# ESPMINERS.net
KiCad netlist of a schematic drawn in EasyEDA
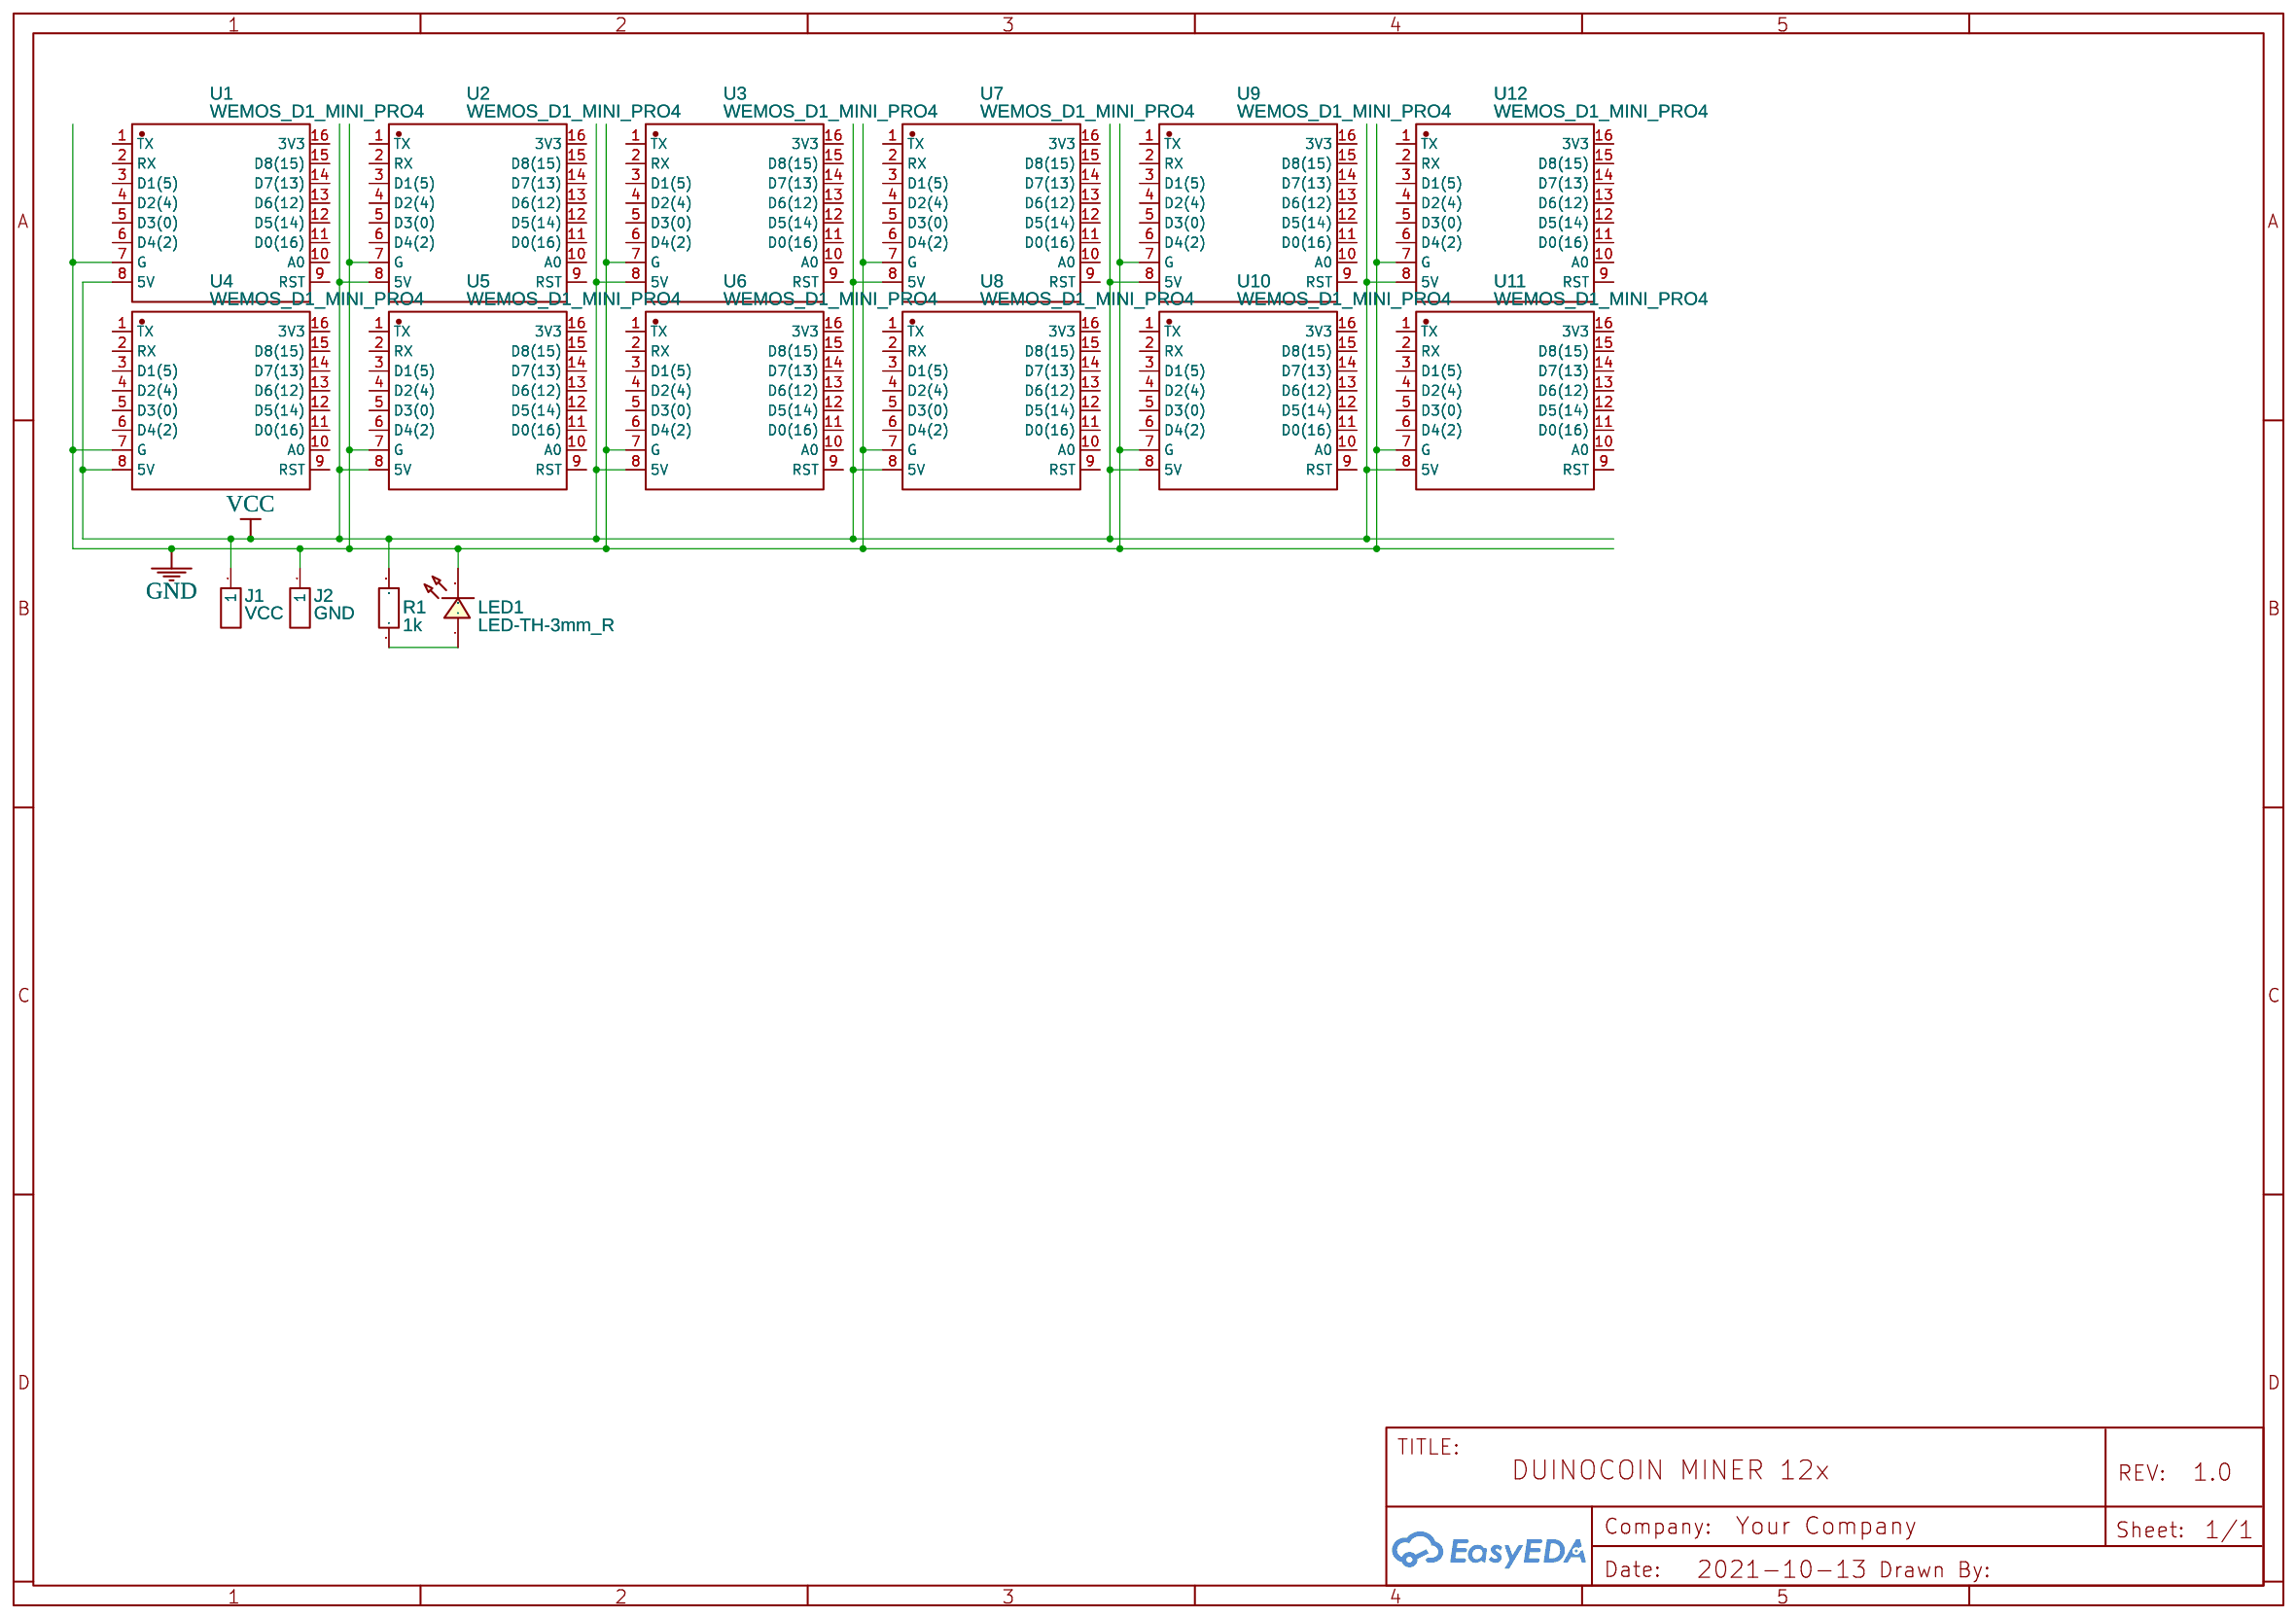
[diagram p0: schematic sheet]

(export (version "E")
  (design (tool "Eeschema 10.0.6"))
  (components
    (comp (ref "J1")
      (value "VCC")
      (fields (field (name "BOM_Supplier Part") "C81276"))
      (libsource (lib "") (part "HDR-M-2.54_1x1"))
    )
    (comp (ref "J2")
      (value "GND")
      (fields (field (name "BOM_Supplier Part") "C81276"))
      (libsource (lib "") (part "HDR-M-2.54_1x1"))
    )
    (comp (ref "LED1")
      (value "LED-TH-3mm_R")
      (fields
        (field (name "BOM_Manufacturer Part") "204-10SDRD/S530-A3-L")
        (field (name "BOM_Supplier Part") "C84774")
      )
      (libsource (lib "") (part "LED-TH-3mm_R"))
    )
    (comp (ref "R1") (value "1k") (libsource (lib "") (part "R_AXIAL-0.3_EU")))
    (comp (ref "U1")
      (value "WEMOS_D1_MINI_PRO4")
      (fields
        (field (name "BOM_Manufacturer Part") "Wemos_D1_mini_Pro4")
        (field (name "BOM_Supplier Part") "C2837266")
      )
      (libsource (lib "") (part "WEMOS_D1_MINI_PRO4"))
    )
    (comp (ref "U2")
      (value "WEMOS_D1_MINI_PRO4")
      (fields
        (field (name "BOM_Manufacturer Part") "Wemos_D1_mini_Pro4")
        (field (name "BOM_Supplier Part") "C2837266")
      )
      (libsource (lib "") (part "WEMOS_D1_MINI_PRO4"))
    )
    (comp (ref "U3")
      (value "WEMOS_D1_MINI_PRO4")
      (fields
        (field (name "BOM_Manufacturer Part") "Wemos_D1_mini_Pro4")
        (field (name "BOM_Supplier Part") "C2837266")
      )
      (libsource (lib "") (part "WEMOS_D1_MINI_PRO4"))
    )
    (comp (ref "U4")
      (value "WEMOS_D1_MINI_PRO4")
      (fields
        (field (name "BOM_Manufacturer Part") "Wemos_D1_mini_Pro4")
        (field (name "BOM_Supplier Part") "C2837266")
      )
      (libsource (lib "") (part "WEMOS_D1_MINI_PRO4"))
    )
    (comp (ref "U5")
      (value "WEMOS_D1_MINI_PRO4")
      (fields
        (field (name "BOM_Manufacturer Part") "Wemos_D1_mini_Pro4")
        (field (name "BOM_Supplier Part") "C2837266")
      )
      (libsource (lib "") (part "WEMOS_D1_MINI_PRO4"))
    )
    (comp (ref "U6")
      (value "WEMOS_D1_MINI_PRO4")
      (fields
        (field (name "BOM_Manufacturer Part") "Wemos_D1_mini_Pro4")
        (field (name "BOM_Supplier Part") "C2837266")
      )
      (libsource (lib "") (part "WEMOS_D1_MINI_PRO4"))
    )
    (comp (ref "U7")
      (value "WEMOS_D1_MINI_PRO4")
      (fields
        (field (name "BOM_Manufacturer Part") "Wemos_D1_mini_Pro4")
        (field (name "BOM_Supplier Part") "C2837266")
      )
      (libsource (lib "") (part "WEMOS_D1_MINI_PRO4"))
    )
    (comp (ref "U8")
      (value "WEMOS_D1_MINI_PRO4")
      (fields
        (field (name "BOM_Manufacturer Part") "Wemos_D1_mini_Pro4")
        (field (name "BOM_Supplier Part") "C2837266")
      )
      (libsource (lib "") (part "WEMOS_D1_MINI_PRO4"))
    )
    (comp (ref "U9")
      (value "WEMOS_D1_MINI_PRO4")
      (fields
        (field (name "BOM_Manufacturer Part") "Wemos_D1_mini_Pro4")
        (field (name "BOM_Supplier Part") "C2837266")
      )
      (libsource (lib "") (part "WEMOS_D1_MINI_PRO4"))
    )
    (comp (ref "U10")
      (value "WEMOS_D1_MINI_PRO4")
      (fields
        (field (name "BOM_Manufacturer Part") "Wemos_D1_mini_Pro4")
        (field (name "BOM_Supplier Part") "C2837266")
      )
      (libsource (lib "") (part "WEMOS_D1_MINI_PRO4"))
    )
    (comp (ref "U11")
      (value "WEMOS_D1_MINI_PRO4")
      (fields
        (field (name "BOM_Manufacturer Part") "Wemos_D1_mini_Pro4")
        (field (name "BOM_Supplier Part") "C2837266")
      )
      (libsource (lib "") (part "WEMOS_D1_MINI_PRO4"))
    )
    (comp (ref "U12")
      (value "WEMOS_D1_MINI_PRO4")
      (fields
        (field (name "BOM_Manufacturer Part") "Wemos_D1_mini_Pro4")
        (field (name "BOM_Supplier Part") "C2837266")
      )
      (libsource (lib "") (part "WEMOS_D1_MINI_PRO4"))
    )
  )
  (nets
    (net (code "1") (name "GND") (class "Default")
      (node (ref "J2") (pin "1") (pinfunction "1_1") (pintype "input"))
      (node (ref "LED1") (pin "2") (pinfunction "2_2") (pintype "unspecified"))
      (node (ref "U1") (pin "7") (pinfunction "G_7") (pintype "unspecified"))
      (node (ref "U10") (pin "7") (pinfunction "G_7") (pintype "unspecified"))
      (node (ref "U11") (pin "7") (pinfunction "G_7") (pintype "unspecified"))
      (node (ref "U12") (pin "7") (pinfunction "G_7") (pintype "unspecified"))
      (node (ref "U2") (pin "7") (pinfunction "G_7") (pintype "unspecified"))
      (node (ref "U3") (pin "7") (pinfunction "G_7") (pintype "unspecified"))
      (node (ref "U4") (pin "7") (pinfunction "G_7") (pintype "unspecified"))
      (node (ref "U5") (pin "7") (pinfunction "G_7") (pintype "unspecified"))
      (node (ref "U6") (pin "7") (pinfunction "G_7") (pintype "unspecified"))
      (node (ref "U7") (pin "7") (pinfunction "G_7") (pintype "unspecified"))
      (node (ref "U8") (pin "7") (pinfunction "G_7") (pintype "unspecified"))
      (node (ref "U9") (pin "7") (pinfunction "G_7") (pintype "unspecified"))
    )
    (net (code "2") (name "Net-(LED1-Pad1)") (class "Default")
      (node (ref "LED1") (pin "1") (pinfunction "1_1") (pintype "unspecified"))
      (node (ref "R1") (pin "1") (pinfunction "1_1") (pintype "unspecified"))
    )
    (net (code "3") (name "VCC") (class "Default")
      (node (ref "J1") (pin "1") (pinfunction "1_1") (pintype "input"))
      (node (ref "R1") (pin "2") (pinfunction "2_2") (pintype "unspecified"))
      (node (ref "U1") (pin "8") (pinfunction "5V_8") (pintype "unspecified"))
      (node (ref "U10") (pin "8") (pinfunction "5V_8") (pintype "unspecified"))
      (node (ref "U11") (pin "8") (pinfunction "5V_8") (pintype "unspecified"))
      (node (ref "U12") (pin "8") (pinfunction "5V_8") (pintype "unspecified"))
      (node (ref "U2") (pin "8") (pinfunction "5V_8") (pintype "unspecified"))
      (node (ref "U3") (pin "8") (pinfunction "5V_8") (pintype "unspecified"))
      (node (ref "U4") (pin "8") (pinfunction "5V_8") (pintype "unspecified"))
      (node (ref "U5") (pin "8") (pinfunction "5V_8") (pintype "unspecified"))
      (node (ref "U6") (pin "8") (pinfunction "5V_8") (pintype "unspecified"))
      (node (ref "U7") (pin "8") (pinfunction "5V_8") (pintype "unspecified"))
      (node (ref "U8") (pin "8") (pinfunction "5V_8") (pintype "unspecified"))
      (node (ref "U9") (pin "8") (pinfunction "5V_8") (pintype "unspecified"))
    )
    (net (code "4") (name "unconnected-(U1-3V3-Pad16)") (class "Default")
      (node (ref "U1") (pin "16") (pinfunction "3V3_16") (pintype "unspecified"))
    )
    (net (code "5") (name "unconnected-(U1-A0-Pad10)") (class "Default")
      (node (ref "U1") (pin "10") (pinfunction "A0_10") (pintype "unspecified"))
    )
    (net (code "6") (name "unconnected-(U1-D0(16)-Pad11)") (class "Default")
      (node (ref "U1") (pin "11") (pinfunction "D0(16)_11") (pintype "unspecified"))
    )
    (net (code "7") (name "unconnected-(U1-D1(5)-Pad3)") (class "Default")
      (node (ref "U1") (pin "3") (pinfunction "D1(5)_3") (pintype "unspecified"))
    )
    (net (code "8") (name "unconnected-(U1-D2(4)-Pad4)") (class "Default")
      (node (ref "U1") (pin "4") (pinfunction "D2(4)_4") (pintype "unspecified"))
    )
    (net (code "9") (name "unconnected-(U1-D3(0)-Pad5)") (class "Default")
      (node (ref "U1") (pin "5") (pinfunction "D3(0)_5") (pintype "unspecified"))
    )
    (net (code "10") (name "unconnected-(U1-D4(2)-Pad6)") (class "Default")
      (node (ref "U1") (pin "6") (pinfunction "D4(2)_6") (pintype "unspecified"))
    )
    (net (code "11") (name "unconnected-(U1-D5(14)-Pad12)") (class "Default")
      (node (ref "U1") (pin "12") (pinfunction "D5(14)_12") (pintype "unspecified"))
    )
    (net (code "12") (name "unconnected-(U1-D6(12)-Pad13)") (class "Default")
      (node (ref "U1") (pin "13") (pinfunction "D6(12)_13") (pintype "unspecified"))
    )
    (net (code "13") (name "unconnected-(U1-D7(13)-Pad14)") (class "Default")
      (node (ref "U1") (pin "14") (pinfunction "D7(13)_14") (pintype "unspecified"))
    )
    (net (code "14") (name "unconnected-(U1-D8(15)-Pad15)") (class "Default")
      (node (ref "U1") (pin "15") (pinfunction "D8(15)_15") (pintype "unspecified"))
    )
    (net (code "15") (name "unconnected-(U1-RST-Pad9)") (class "Default")
      (node (ref "U1") (pin "9") (pinfunction "RST_9") (pintype "unspecified"))
    )
    (net (code "16") (name "unconnected-(U1-RX-Pad2)") (class "Default")
      (node (ref "U1") (pin "2") (pinfunction "RX_2") (pintype "unspecified"))
    )
    (net (code "17") (name "unconnected-(U1-TX-Pad1)") (class "Default")
      (node (ref "U1") (pin "1") (pinfunction "TX_1") (pintype "unspecified"))
    )
    (net (code "18") (name "unconnected-(U2-3V3-Pad16)") (class "Default")
      (node (ref "U2") (pin "16") (pinfunction "3V3_16") (pintype "unspecified"))
    )
    (net (code "19") (name "unconnected-(U2-A0-Pad10)") (class "Default")
      (node (ref "U2") (pin "10") (pinfunction "A0_10") (pintype "unspecified"))
    )
    (net (code "20") (name "unconnected-(U2-D0(16)-Pad11)") (class "Default")
      (node (ref "U2") (pin "11") (pinfunction "D0(16)_11") (pintype "unspecified"))
    )
    (net (code "21") (name "unconnected-(U2-D1(5)-Pad3)") (class "Default")
      (node (ref "U2") (pin "3") (pinfunction "D1(5)_3") (pintype "unspecified"))
    )
    (net (code "22") (name "unconnected-(U2-D2(4)-Pad4)") (class "Default")
      (node (ref "U2") (pin "4") (pinfunction "D2(4)_4") (pintype "unspecified"))
    )
    (net (code "23") (name "unconnected-(U2-D3(0)-Pad5)") (class "Default")
      (node (ref "U2") (pin "5") (pinfunction "D3(0)_5") (pintype "unspecified"))
    )
    (net (code "24") (name "unconnected-(U2-D4(2)-Pad6)") (class "Default")
      (node (ref "U2") (pin "6") (pinfunction "D4(2)_6") (pintype "unspecified"))
    )
    (net (code "25") (name "unconnected-(U2-D5(14)-Pad12)") (class "Default")
      (node (ref "U2") (pin "12") (pinfunction "D5(14)_12") (pintype "unspecified"))
    )
    (net (code "26") (name "unconnected-(U2-D6(12)-Pad13)") (class "Default")
      (node (ref "U2") (pin "13") (pinfunction "D6(12)_13") (pintype "unspecified"))
    )
    (net (code "27") (name "unconnected-(U2-D7(13)-Pad14)") (class "Default")
      (node (ref "U2") (pin "14") (pinfunction "D7(13)_14") (pintype "unspecified"))
    )
    (net (code "28") (name "unconnected-(U2-D8(15)-Pad15)") (class "Default")
      (node (ref "U2") (pin "15") (pinfunction "D8(15)_15") (pintype "unspecified"))
    )
    (net (code "29") (name "unconnected-(U2-RST-Pad9)") (class "Default")
      (node (ref "U2") (pin "9") (pinfunction "RST_9") (pintype "unspecified"))
    )
    (net (code "30") (name "unconnected-(U2-RX-Pad2)") (class "Default")
      (node (ref "U2") (pin "2") (pinfunction "RX_2") (pintype "unspecified"))
    )
    (net (code "31") (name "unconnected-(U2-TX-Pad1)") (class "Default")
      (node (ref "U2") (pin "1") (pinfunction "TX_1") (pintype "unspecified"))
    )
    (net (code "32") (name "unconnected-(U3-3V3-Pad16)") (class "Default")
      (node (ref "U3") (pin "16") (pinfunction "3V3_16") (pintype "unspecified"))
    )
    (net (code "33") (name "unconnected-(U3-A0-Pad10)") (class "Default")
      (node (ref "U3") (pin "10") (pinfunction "A0_10") (pintype "unspecified"))
    )
    (net (code "34") (name "unconnected-(U3-D0(16)-Pad11)") (class "Default")
      (node (ref "U3") (pin "11") (pinfunction "D0(16)_11") (pintype "unspecified"))
    )
    (net (code "35") (name "unconnected-(U3-D1(5)-Pad3)") (class "Default")
      (node (ref "U3") (pin "3") (pinfunction "D1(5)_3") (pintype "unspecified"))
    )
    (net (code "36") (name "unconnected-(U3-D2(4)-Pad4)") (class "Default")
      (node (ref "U3") (pin "4") (pinfunction "D2(4)_4") (pintype "unspecified"))
    )
    (net (code "37") (name "unconnected-(U3-D3(0)-Pad5)") (class "Default")
      (node (ref "U3") (pin "5") (pinfunction "D3(0)_5") (pintype "unspecified"))
    )
    (net (code "38") (name "unconnected-(U3-D4(2)-Pad6)") (class "Default")
      (node (ref "U3") (pin "6") (pinfunction "D4(2)_6") (pintype "unspecified"))
    )
    (net (code "39") (name "unconnected-(U3-D5(14)-Pad12)") (class "Default")
      (node (ref "U3") (pin "12") (pinfunction "D5(14)_12") (pintype "unspecified"))
    )
    (net (code "40") (name "unconnected-(U3-D6(12)-Pad13)") (class "Default")
      (node (ref "U3") (pin "13") (pinfunction "D6(12)_13") (pintype "unspecified"))
    )
    (net (code "41") (name "unconnected-(U3-D7(13)-Pad14)") (class "Default")
      (node (ref "U3") (pin "14") (pinfunction "D7(13)_14") (pintype "unspecified"))
    )
    (net (code "42") (name "unconnected-(U3-D8(15)-Pad15)") (class "Default")
      (node (ref "U3") (pin "15") (pinfunction "D8(15)_15") (pintype "unspecified"))
    )
    (net (code "43") (name "unconnected-(U3-RST-Pad9)") (class "Default")
      (node (ref "U3") (pin "9") (pinfunction "RST_9") (pintype "unspecified"))
    )
    (net (code "44") (name "unconnected-(U3-RX-Pad2)") (class "Default")
      (node (ref "U3") (pin "2") (pinfunction "RX_2") (pintype "unspecified"))
    )
    (net (code "45") (name "unconnected-(U3-TX-Pad1)") (class "Default")
      (node (ref "U3") (pin "1") (pinfunction "TX_1") (pintype "unspecified"))
    )
    (net (code "46") (name "unconnected-(U4-3V3-Pad16)") (class "Default")
      (node (ref "U4") (pin "16") (pinfunction "3V3_16") (pintype "unspecified"))
    )
    (net (code "47") (name "unconnected-(U4-A0-Pad10)") (class "Default")
      (node (ref "U4") (pin "10") (pinfunction "A0_10") (pintype "unspecified"))
    )
    (net (code "48") (name "unconnected-(U4-D0(16)-Pad11)") (class "Default")
      (node (ref "U4") (pin "11") (pinfunction "D0(16)_11") (pintype "unspecified"))
    )
    (net (code "49") (name "unconnected-(U4-D1(5)-Pad3)") (class "Default")
      (node (ref "U4") (pin "3") (pinfunction "D1(5)_3") (pintype "unspecified"))
    )
    (net (code "50") (name "unconnected-(U4-D2(4)-Pad4)") (class "Default")
      (node (ref "U4") (pin "4") (pinfunction "D2(4)_4") (pintype "unspecified"))
    )
    (net (code "51") (name "unconnected-(U4-D3(0)-Pad5)") (class "Default")
      (node (ref "U4") (pin "5") (pinfunction "D3(0)_5") (pintype "unspecified"))
    )
    (net (code "52") (name "unconnected-(U4-D4(2)-Pad6)") (class "Default")
      (node (ref "U4") (pin "6") (pinfunction "D4(2)_6") (pintype "unspecified"))
    )
    (net (code "53") (name "unconnected-(U4-D5(14)-Pad12)") (class "Default")
      (node (ref "U4") (pin "12") (pinfunction "D5(14)_12") (pintype "unspecified"))
    )
    (net (code "54") (name "unconnected-(U4-D6(12)-Pad13)") (class "Default")
      (node (ref "U4") (pin "13") (pinfunction "D6(12)_13") (pintype "unspecified"))
    )
    (net (code "55") (name "unconnected-(U4-D7(13)-Pad14)") (class "Default")
      (node (ref "U4") (pin "14") (pinfunction "D7(13)_14") (pintype "unspecified"))
    )
    (net (code "56") (name "unconnected-(U4-D8(15)-Pad15)") (class "Default")
      (node (ref "U4") (pin "15") (pinfunction "D8(15)_15") (pintype "unspecified"))
    )
    (net (code "57") (name "unconnected-(U4-RST-Pad9)") (class "Default")
      (node (ref "U4") (pin "9") (pinfunction "RST_9") (pintype "unspecified"))
    )
    (net (code "58") (name "unconnected-(U4-RX-Pad2)") (class "Default")
      (node (ref "U4") (pin "2") (pinfunction "RX_2") (pintype "unspecified"))
    )
    (net (code "59") (name "unconnected-(U4-TX-Pad1)") (class "Default")
      (node (ref "U4") (pin "1") (pinfunction "TX_1") (pintype "unspecified"))
    )
    (net (code "60") (name "unconnected-(U5-3V3-Pad16)") (class "Default")
      (node (ref "U5") (pin "16") (pinfunction "3V3_16") (pintype "unspecified"))
    )
    (net (code "61") (name "unconnected-(U5-A0-Pad10)") (class "Default")
      (node (ref "U5") (pin "10") (pinfunction "A0_10") (pintype "unspecified"))
    )
    (net (code "62") (name "unconnected-(U5-D0(16)-Pad11)") (class "Default")
      (node (ref "U5") (pin "11") (pinfunction "D0(16)_11") (pintype "unspecified"))
    )
    (net (code "63") (name "unconnected-(U5-D1(5)-Pad3)") (class "Default")
      (node (ref "U5") (pin "3") (pinfunction "D1(5)_3") (pintype "unspecified"))
    )
    (net (code "64") (name "unconnected-(U5-D2(4)-Pad4)") (class "Default")
      (node (ref "U5") (pin "4") (pinfunction "D2(4)_4") (pintype "unspecified"))
    )
    (net (code "65") (name "unconnected-(U5-D3(0)-Pad5)") (class "Default")
      (node (ref "U5") (pin "5") (pinfunction "D3(0)_5") (pintype "unspecified"))
    )
    (net (code "66") (name "unconnected-(U5-D4(2)-Pad6)") (class "Default")
      (node (ref "U5") (pin "6") (pinfunction "D4(2)_6") (pintype "unspecified"))
    )
    (net (code "67") (name "unconnected-(U5-D5(14)-Pad12)") (class "Default")
      (node (ref "U5") (pin "12") (pinfunction "D5(14)_12") (pintype "unspecified"))
    )
    (net (code "68") (name "unconnected-(U5-D6(12)-Pad13)") (class "Default")
      (node (ref "U5") (pin "13") (pinfunction "D6(12)_13") (pintype "unspecified"))
    )
    (net (code "69") (name "unconnected-(U5-D7(13)-Pad14)") (class "Default")
      (node (ref "U5") (pin "14") (pinfunction "D7(13)_14") (pintype "unspecified"))
    )
    (net (code "70") (name "unconnected-(U5-D8(15)-Pad15)") (class "Default")
      (node (ref "U5") (pin "15") (pinfunction "D8(15)_15") (pintype "unspecified"))
    )
    (net (code "71") (name "unconnected-(U5-RST-Pad9)") (class "Default")
      (node (ref "U5") (pin "9") (pinfunction "RST_9") (pintype "unspecified"))
    )
    (net (code "72") (name "unconnected-(U5-RX-Pad2)") (class "Default")
      (node (ref "U5") (pin "2") (pinfunction "RX_2") (pintype "unspecified"))
    )
    (net (code "73") (name "unconnected-(U5-TX-Pad1)") (class "Default")
      (node (ref "U5") (pin "1") (pinfunction "TX_1") (pintype "unspecified"))
    )
    (net (code "74") (name "unconnected-(U6-3V3-Pad16)") (class "Default")
      (node (ref "U6") (pin "16") (pinfunction "3V3_16") (pintype "unspecified"))
    )
    (net (code "75") (name "unconnected-(U6-A0-Pad10)") (class "Default")
      (node (ref "U6") (pin "10") (pinfunction "A0_10") (pintype "unspecified"))
    )
    (net (code "76") (name "unconnected-(U6-D0(16)-Pad11)") (class "Default")
      (node (ref "U6") (pin "11") (pinfunction "D0(16)_11") (pintype "unspecified"))
    )
    (net (code "77") (name "unconnected-(U6-D1(5)-Pad3)") (class "Default")
      (node (ref "U6") (pin "3") (pinfunction "D1(5)_3") (pintype "unspecified"))
    )
    (net (code "78") (name "unconnected-(U6-D2(4)-Pad4)") (class "Default")
      (node (ref "U6") (pin "4") (pinfunction "D2(4)_4") (pintype "unspecified"))
    )
    (net (code "79") (name "unconnected-(U6-D3(0)-Pad5)") (class "Default")
      (node (ref "U6") (pin "5") (pinfunction "D3(0)_5") (pintype "unspecified"))
    )
    (net (code "80") (name "unconnected-(U6-D4(2)-Pad6)") (class "Default")
      (node (ref "U6") (pin "6") (pinfunction "D4(2)_6") (pintype "unspecified"))
    )
    (net (code "81") (name "unconnected-(U6-D5(14)-Pad12)") (class "Default")
      (node (ref "U6") (pin "12") (pinfunction "D5(14)_12") (pintype "unspecified"))
    )
    (net (code "82") (name "unconnected-(U6-D6(12)-Pad13)") (class "Default")
      (node (ref "U6") (pin "13") (pinfunction "D6(12)_13") (pintype "unspecified"))
    )
    (net (code "83") (name "unconnected-(U6-D7(13)-Pad14)") (class "Default")
      (node (ref "U6") (pin "14") (pinfunction "D7(13)_14") (pintype "unspecified"))
    )
    (net (code "84") (name "unconnected-(U6-D8(15)-Pad15)") (class "Default")
      (node (ref "U6") (pin "15") (pinfunction "D8(15)_15") (pintype "unspecified"))
    )
    (net (code "85") (name "unconnected-(U6-RST-Pad9)") (class "Default")
      (node (ref "U6") (pin "9") (pinfunction "RST_9") (pintype "unspecified"))
    )
    (net (code "86") (name "unconnected-(U6-RX-Pad2)") (class "Default")
      (node (ref "U6") (pin "2") (pinfunction "RX_2") (pintype "unspecified"))
    )
    (net (code "87") (name "unconnected-(U6-TX-Pad1)") (class "Default")
      (node (ref "U6") (pin "1") (pinfunction "TX_1") (pintype "unspecified"))
    )
    (net (code "88") (name "unconnected-(U7-3V3-Pad16)") (class "Default")
      (node (ref "U7") (pin "16") (pinfunction "3V3_16") (pintype "unspecified"))
    )
    (net (code "89") (name "unconnected-(U7-A0-Pad10)") (class "Default")
      (node (ref "U7") (pin "10") (pinfunction "A0_10") (pintype "unspecified"))
    )
    (net (code "90") (name "unconnected-(U7-D0(16)-Pad11)") (class "Default")
      (node (ref "U7") (pin "11") (pinfunction "D0(16)_11") (pintype "unspecified"))
    )
    (net (code "91") (name "unconnected-(U7-D1(5)-Pad3)") (class "Default")
      (node (ref "U7") (pin "3") (pinfunction "D1(5)_3") (pintype "unspecified"))
    )
    (net (code "92") (name "unconnected-(U7-D2(4)-Pad4)") (class "Default")
      (node (ref "U7") (pin "4") (pinfunction "D2(4)_4") (pintype "unspecified"))
    )
    (net (code "93") (name "unconnected-(U7-D3(0)-Pad5)") (class "Default")
      (node (ref "U7") (pin "5") (pinfunction "D3(0)_5") (pintype "unspecified"))
    )
    (net (code "94") (name "unconnected-(U7-D4(2)-Pad6)") (class "Default")
      (node (ref "U7") (pin "6") (pinfunction "D4(2)_6") (pintype "unspecified"))
    )
    (net (code "95") (name "unconnected-(U7-D5(14)-Pad12)") (class "Default")
      (node (ref "U7") (pin "12") (pinfunction "D5(14)_12") (pintype "unspecified"))
    )
    (net (code "96") (name "unconnected-(U7-D6(12)-Pad13)") (class "Default")
      (node (ref "U7") (pin "13") (pinfunction "D6(12)_13") (pintype "unspecified"))
    )
    (net (code "97") (name "unconnected-(U7-D7(13)-Pad14)") (class "Default")
      (node (ref "U7") (pin "14") (pinfunction "D7(13)_14") (pintype "unspecified"))
    )
    (net (code "98") (name "unconnected-(U7-D8(15)-Pad15)") (class "Default")
      (node (ref "U7") (pin "15") (pinfunction "D8(15)_15") (pintype "unspecified"))
    )
    (net (code "99") (name "unconnected-(U7-RST-Pad9)") (class "Default")
      (node (ref "U7") (pin "9") (pinfunction "RST_9") (pintype "unspecified"))
    )
    (net (code "100") (name "unconnected-(U7-RX-Pad2)") (class "Default")
      (node (ref "U7") (pin "2") (pinfunction "RX_2") (pintype "unspecified"))
    )
    (net (code "101") (name "unconnected-(U7-TX-Pad1)") (class "Default")
      (node (ref "U7") (pin "1") (pinfunction "TX_1") (pintype "unspecified"))
    )
    (net (code "102") (name "unconnected-(U8-3V3-Pad16)") (class "Default")
      (node (ref "U8") (pin "16") (pinfunction "3V3_16") (pintype "unspecified"))
    )
    (net (code "103") (name "unconnected-(U8-A0-Pad10)") (class "Default")
      (node (ref "U8") (pin "10") (pinfunction "A0_10") (pintype "unspecified"))
    )
    (net (code "104") (name "unconnected-(U8-D0(16)-Pad11)") (class "Default")
      (node (ref "U8") (pin "11") (pinfunction "D0(16)_11") (pintype "unspecified"))
    )
    (net (code "105") (name "unconnected-(U8-D1(5)-Pad3)") (class "Default")
      (node (ref "U8") (pin "3") (pinfunction "D1(5)_3") (pintype "unspecified"))
    )
    (net (code "106") (name "unconnected-(U8-D2(4)-Pad4)") (class "Default")
      (node (ref "U8") (pin "4") (pinfunction "D2(4)_4") (pintype "unspecified"))
    )
    (net (code "107") (name "unconnected-(U8-D3(0)-Pad5)") (class "Default")
      (node (ref "U8") (pin "5") (pinfunction "D3(0)_5") (pintype "unspecified"))
    )
    (net (code "108") (name "unconnected-(U8-D4(2)-Pad6)") (class "Default")
      (node (ref "U8") (pin "6") (pinfunction "D4(2)_6") (pintype "unspecified"))
    )
    (net (code "109") (name "unconnected-(U8-D5(14)-Pad12)") (class "Default")
      (node (ref "U8") (pin "12") (pinfunction "D5(14)_12") (pintype "unspecified"))
    )
    (net (code "110") (name "unconnected-(U8-D6(12)-Pad13)") (class "Default")
      (node (ref "U8") (pin "13") (pinfunction "D6(12)_13") (pintype "unspecified"))
    )
    (net (code "111") (name "unconnected-(U8-D7(13)-Pad14)") (class "Default")
      (node (ref "U8") (pin "14") (pinfunction "D7(13)_14") (pintype "unspecified"))
    )
    (net (code "112") (name "unconnected-(U8-D8(15)-Pad15)") (class "Default")
      (node (ref "U8") (pin "15") (pinfunction "D8(15)_15") (pintype "unspecified"))
    )
    (net (code "113") (name "unconnected-(U8-RST-Pad9)") (class "Default")
      (node (ref "U8") (pin "9") (pinfunction "RST_9") (pintype "unspecified"))
    )
    (net (code "114") (name "unconnected-(U8-RX-Pad2)") (class "Default")
      (node (ref "U8") (pin "2") (pinfunction "RX_2") (pintype "unspecified"))
    )
    (net (code "115") (name "unconnected-(U8-TX-Pad1)") (class "Default")
      (node (ref "U8") (pin "1") (pinfunction "TX_1") (pintype "unspecified"))
    )
    (net (code "116") (name "unconnected-(U9-3V3-Pad16)") (class "Default")
      (node (ref "U9") (pin "16") (pinfunction "3V3_16") (pintype "unspecified"))
    )
    (net (code "117") (name "unconnected-(U9-A0-Pad10)") (class "Default")
      (node (ref "U9") (pin "10") (pinfunction "A0_10") (pintype "unspecified"))
    )
    (net (code "118") (name "unconnected-(U9-D0(16)-Pad11)") (class "Default")
      (node (ref "U9") (pin "11") (pinfunction "D0(16)_11") (pintype "unspecified"))
    )
    (net (code "119") (name "unconnected-(U9-D1(5)-Pad3)") (class "Default")
      (node (ref "U9") (pin "3") (pinfunction "D1(5)_3") (pintype "unspecified"))
    )
    (net (code "120") (name "unconnected-(U9-D2(4)-Pad4)") (class "Default")
      (node (ref "U9") (pin "4") (pinfunction "D2(4)_4") (pintype "unspecified"))
    )
    (net (code "121") (name "unconnected-(U9-D3(0)-Pad5)") (class "Default")
      (node (ref "U9") (pin "5") (pinfunction "D3(0)_5") (pintype "unspecified"))
    )
    (net (code "122") (name "unconnected-(U9-D4(2)-Pad6)") (class "Default")
      (node (ref "U9") (pin "6") (pinfunction "D4(2)_6") (pintype "unspecified"))
    )
    (net (code "123") (name "unconnected-(U9-D5(14)-Pad12)") (class "Default")
      (node (ref "U9") (pin "12") (pinfunction "D5(14)_12") (pintype "unspecified"))
    )
    (net (code "124") (name "unconnected-(U9-D6(12)-Pad13)") (class "Default")
      (node (ref "U9") (pin "13") (pinfunction "D6(12)_13") (pintype "unspecified"))
    )
    (net (code "125") (name "unconnected-(U9-D7(13)-Pad14)") (class "Default")
      (node (ref "U9") (pin "14") (pinfunction "D7(13)_14") (pintype "unspecified"))
    )
    (net (code "126") (name "unconnected-(U9-D8(15)-Pad15)") (class "Default")
      (node (ref "U9") (pin "15") (pinfunction "D8(15)_15") (pintype "unspecified"))
    )
    (net (code "127") (name "unconnected-(U9-RST-Pad9)") (class "Default")
      (node (ref "U9") (pin "9") (pinfunction "RST_9") (pintype "unspecified"))
    )
    (net (code "128") (name "unconnected-(U9-RX-Pad2)") (class "Default")
      (node (ref "U9") (pin "2") (pinfunction "RX_2") (pintype "unspecified"))
    )
    (net (code "129") (name "unconnected-(U9-TX-Pad1)") (class "Default")
      (node (ref "U9") (pin "1") (pinfunction "TX_1") (pintype "unspecified"))
    )
    (net (code "130") (name "unconnected-(U10-3V3-Pad16)") (class "Default")
      (node (ref "U10") (pin "16") (pinfunction "3V3_16") (pintype "unspecified"))
    )
    (net (code "131") (name "unconnected-(U10-A0-Pad10)") (class "Default")
      (node (ref "U10") (pin "10") (pinfunction "A0_10") (pintype "unspecified"))
    )
    (net (code "132") (name "unconnected-(U10-D0(16)-Pad11)") (class "Default")
      (node (ref "U10") (pin "11") (pinfunction "D0(16)_11") (pintype "unspecified"))
    )
    (net (code "133") (name "unconnected-(U10-D1(5)-Pad3)") (class "Default")
      (node (ref "U10") (pin "3") (pinfunction "D1(5)_3") (pintype "unspecified"))
    )
    (net (code "134") (name "unconnected-(U10-D2(4)-Pad4)") (class "Default")
      (node (ref "U10") (pin "4") (pinfunction "D2(4)_4") (pintype "unspecified"))
    )
    (net (code "135") (name "unconnected-(U10-D3(0)-Pad5)") (class "Default")
      (node (ref "U10") (pin "5") (pinfunction "D3(0)_5") (pintype "unspecified"))
    )
    (net (code "136") (name "unconnected-(U10-D4(2)-Pad6)") (class "Default")
      (node (ref "U10") (pin "6") (pinfunction "D4(2)_6") (pintype "unspecified"))
    )
    (net (code "137") (name "unconnected-(U10-D5(14)-Pad12)") (class "Default")
      (node (ref "U10") (pin "12") (pinfunction "D5(14)_12") (pintype "unspecified"))
    )
    (net (code "138") (name "unconnected-(U10-D6(12)-Pad13)") (class "Default")
      (node (ref "U10") (pin "13") (pinfunction "D6(12)_13") (pintype "unspecified"))
    )
    (net (code "139") (name "unconnected-(U10-D7(13)-Pad14)") (class "Default")
      (node (ref "U10") (pin "14") (pinfunction "D7(13)_14") (pintype "unspecified"))
    )
    (net (code "140") (name "unconnected-(U10-D8(15)-Pad15)") (class "Default")
      (node (ref "U10") (pin "15") (pinfunction "D8(15)_15") (pintype "unspecified"))
    )
    (net (code "141") (name "unconnected-(U10-RST-Pad9)") (class "Default")
      (node (ref "U10") (pin "9") (pinfunction "RST_9") (pintype "unspecified"))
    )
    (net (code "142") (name "unconnected-(U10-RX-Pad2)") (class "Default")
      (node (ref "U10") (pin "2") (pinfunction "RX_2") (pintype "unspecified"))
    )
    (net (code "143") (name "unconnected-(U10-TX-Pad1)") (class "Default")
      (node (ref "U10") (pin "1") (pinfunction "TX_1") (pintype "unspecified"))
    )
    (net (code "144") (name "unconnected-(U11-3V3-Pad16)") (class "Default")
      (node (ref "U11") (pin "16") (pinfunction "3V3_16") (pintype "unspecified"))
    )
    (net (code "145") (name "unconnected-(U11-A0-Pad10)") (class "Default")
      (node (ref "U11") (pin "10") (pinfunction "A0_10") (pintype "unspecified"))
    )
    (net (code "146") (name "unconnected-(U11-D0(16)-Pad11)") (class "Default")
      (node (ref "U11") (pin "11") (pinfunction "D0(16)_11") (pintype "unspecified"))
    )
    (net (code "147") (name "unconnected-(U11-D1(5)-Pad3)") (class "Default")
      (node (ref "U11") (pin "3") (pinfunction "D1(5)_3") (pintype "unspecified"))
    )
    (net (code "148") (name "unconnected-(U11-D2(4)-Pad4)") (class "Default")
      (node (ref "U11") (pin "4") (pinfunction "D2(4)_4") (pintype "unspecified"))
    )
    (net (code "149") (name "unconnected-(U11-D3(0)-Pad5)") (class "Default")
      (node (ref "U11") (pin "5") (pinfunction "D3(0)_5") (pintype "unspecified"))
    )
    (net (code "150") (name "unconnected-(U11-D4(2)-Pad6)") (class "Default")
      (node (ref "U11") (pin "6") (pinfunction "D4(2)_6") (pintype "unspecified"))
    )
    (net (code "151") (name "unconnected-(U11-D5(14)-Pad12)") (class "Default")
      (node (ref "U11") (pin "12") (pinfunction "D5(14)_12") (pintype "unspecified"))
    )
    (net (code "152") (name "unconnected-(U11-D6(12)-Pad13)") (class "Default")
      (node (ref "U11") (pin "13") (pinfunction "D6(12)_13") (pintype "unspecified"))
    )
    (net (code "153") (name "unconnected-(U11-D7(13)-Pad14)") (class "Default")
      (node (ref "U11") (pin "14") (pinfunction "D7(13)_14") (pintype "unspecified"))
    )
    (net (code "154") (name "unconnected-(U11-D8(15)-Pad15)") (class "Default")
      (node (ref "U11") (pin "15") (pinfunction "D8(15)_15") (pintype "unspecified"))
    )
    (net (code "155") (name "unconnected-(U11-RST-Pad9)") (class "Default")
      (node (ref "U11") (pin "9") (pinfunction "RST_9") (pintype "unspecified"))
    )
    (net (code "156") (name "unconnected-(U11-RX-Pad2)") (class "Default")
      (node (ref "U11") (pin "2") (pinfunction "RX_2") (pintype "unspecified"))
    )
    (net (code "157") (name "unconnected-(U11-TX-Pad1)") (class "Default")
      (node (ref "U11") (pin "1") (pinfunction "TX_1") (pintype "unspecified"))
    )
    (net (code "158") (name "unconnected-(U12-3V3-Pad16)") (class "Default")
      (node (ref "U12") (pin "16") (pinfunction "3V3_16") (pintype "unspecified"))
    )
    (net (code "159") (name "unconnected-(U12-A0-Pad10)") (class "Default")
      (node (ref "U12") (pin "10") (pinfunction "A0_10") (pintype "unspecified"))
    )
    (net (code "160") (name "unconnected-(U12-D0(16)-Pad11)") (class "Default")
      (node (ref "U12") (pin "11") (pinfunction "D0(16)_11") (pintype "unspecified"))
    )
    (net (code "161") (name "unconnected-(U12-D1(5)-Pad3)") (class "Default")
      (node (ref "U12") (pin "3") (pinfunction "D1(5)_3") (pintype "unspecified"))
    )
    (net (code "162") (name "unconnected-(U12-D2(4)-Pad4)") (class "Default")
      (node (ref "U12") (pin "4") (pinfunction "D2(4)_4") (pintype "unspecified"))
    )
    (net (code "163") (name "unconnected-(U12-D3(0)-Pad5)") (class "Default")
      (node (ref "U12") (pin "5") (pinfunction "D3(0)_5") (pintype "unspecified"))
    )
    (net (code "164") (name "unconnected-(U12-D4(2)-Pad6)") (class "Default")
      (node (ref "U12") (pin "6") (pinfunction "D4(2)_6") (pintype "unspecified"))
    )
    (net (code "165") (name "unconnected-(U12-D5(14)-Pad12)") (class "Default")
      (node (ref "U12") (pin "12") (pinfunction "D5(14)_12") (pintype "unspecified"))
    )
    (net (code "166") (name "unconnected-(U12-D6(12)-Pad13)") (class "Default")
      (node (ref "U12") (pin "13") (pinfunction "D6(12)_13") (pintype "unspecified"))
    )
    (net (code "167") (name "unconnected-(U12-D7(13)-Pad14)") (class "Default")
      (node (ref "U12") (pin "14") (pinfunction "D7(13)_14") (pintype "unspecified"))
    )
    (net (code "168") (name "unconnected-(U12-D8(15)-Pad15)") (class "Default")
      (node (ref "U12") (pin "15") (pinfunction "D8(15)_15") (pintype "unspecified"))
    )
    (net (code "169") (name "unconnected-(U12-RST-Pad9)") (class "Default")
      (node (ref "U12") (pin "9") (pinfunction "RST_9") (pintype "unspecified"))
    )
    (net (code "170") (name "unconnected-(U12-RX-Pad2)") (class "Default")
      (node (ref "U12") (pin "2") (pinfunction "RX_2") (pintype "unspecified"))
    )
    (net (code "171") (name "unconnected-(U12-TX-Pad1)") (class "Default")
      (node (ref "U12") (pin "1") (pinfunction "TX_1") (pintype "unspecified"))
    )
  )
)
